# ADC_LCD_PROJECT.net
KiCad netlist of a schematic drawn in Altium Designer
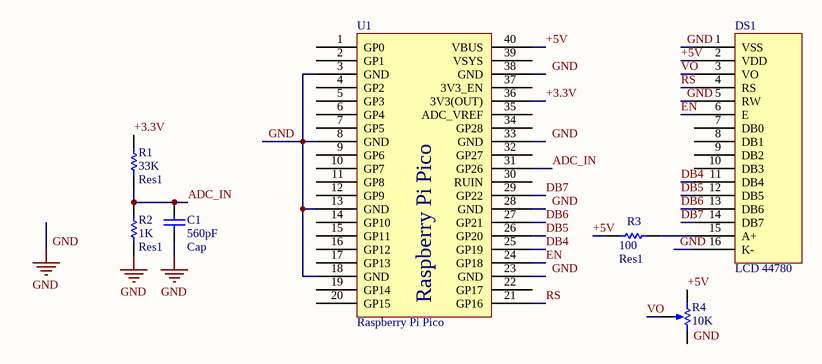
[diagram p0: ADC_LCD_PROJECT.SchDoc]

(export (version "E")
  (design (tool "Eeschema 10.0.6"))
  (components
    (comp (ref "C1")
      (value "Cap")
      (footprint "RAD-0.3")
      (description "Capacitor")
      (fields (field (name "ALTIUM_VALUE") "560pF") (field (name "PUBLISHER") "Altium Limited"))
      (libsource (lib "Miscellaneous Devices") (part "Cap"))
    )
    (comp (ref "DS1")
      (value "LCD 44780")
      (footprint "OLED 16x2")
      (libsource (lib "ECE Lib 22") (part "LCD 44780"))
    )
    (comp (ref "R1")
      (value "Res1")
      (footprint "AXIAL-0.3")
      (description "Resistor")
      (fields (field (name "ALTIUM_VALUE") "33K") (field (name "PUBLISHER") "Altium Limited"))
      (libsource (lib "Miscellaneous Devices") (part "Res1"))
    )
    (comp (ref "R2")
      (value "Res1")
      (footprint "AXIAL-0.3")
      (description "Resistor")
      (fields (field (name "ALTIUM_VALUE") "1K") (field (name "PUBLISHER") "Altium Limited"))
      (libsource (lib "Miscellaneous Devices") (part "Res1"))
    )
    (comp (ref "R3")
      (value "Res1")
      (footprint "AXIAL-0.3")
      (description "Resistor")
      (fields (field (name "ALTIUM_VALUE") "100") (field (name "PUBLISHER") "Altium Limited"))
      (libsource (lib "Miscellaneous Devices") (part "Res1"))
    )
    (comp (ref "R4")
      (value "10K")
      (footprint "POT inline wide")
      (description "Potentiometer")
      (fields (field (name "Comment") "RPot_1") (field (name "PUBLISHER") "Altium Limited"))
      (libsource (lib "ECE Lib 22") (part "RPot_3"))
    )
    (comp (ref "U1")
      (value "Raspberry Pi Pico")
      (footprint "Raspberry Pi Pico")
      (libsource (lib "ECE Lib 22") (part "Raspberry Pi Pico"))
    )
  )
  (nets
    (net (code "1") (name "/+3.3V") (class "Default")
      (node (ref "R1") (pin "2") (pinfunction "2_2") (pintype "passive"))
      (node (ref "U1") (pin "36") (pinfunction "3V3(OUT)_36") (pintype "passive"))
    )
    (net (code "2") (name "/+5V") (class "Default")
      (node (ref "DS1") (pin "2") (pinfunction "VDD_2") (pintype "passive"))
      (node (ref "R3") (pin "1") (pinfunction "1_1") (pintype "passive"))
      (node (ref "R4") (pin "1") (pinfunction "TOP_1") (pintype "passive"))
      (node (ref "U1") (pin "40") (pinfunction "VBUS_40") (pintype "passive"))
    )
    (net (code "3") (name "/ADC_IN") (class "Default")
      (node (ref "C1") (pin "2") (pinfunction "2_2") (pintype "passive"))
      (node (ref "R1") (pin "1") (pinfunction "1_1") (pintype "passive"))
      (node (ref "R2") (pin "2") (pinfunction "2_2") (pintype "passive"))
      (node (ref "U1") (pin "31") (pinfunction "GP26_31") (pintype "passive"))
    )
    (net (code "4") (name "/DB4") (class "Default")
      (node (ref "DS1") (pin "11") (pinfunction "DB4_11") (pintype "passive"))
      (node (ref "U1") (pin "25") (pinfunction "GP19_25") (pintype "passive"))
    )
    (net (code "5") (name "/DB5") (class "Default")
      (node (ref "DS1") (pin "12") (pinfunction "DB5_12") (pintype "passive"))
      (node (ref "U1") (pin "26") (pinfunction "GP20_26") (pintype "passive"))
    )
    (net (code "6") (name "/DB6") (class "Default")
      (node (ref "DS1") (pin "13") (pinfunction "DB6_13") (pintype "passive"))
      (node (ref "U1") (pin "27") (pinfunction "GP21_27") (pintype "passive"))
    )
    (net (code "7") (name "/DB7") (class "Default")
      (node (ref "DS1") (pin "14") (pinfunction "DB7_14") (pintype "passive"))
      (node (ref "U1") (pin "29") (pinfunction "GP22_29") (pintype "passive"))
    )
    (net (code "8") (name "/EN") (class "Default")
      (node (ref "DS1") (pin "6") (pinfunction "E_6") (pintype "passive"))
      (node (ref "U1") (pin "24") (pinfunction "GP18_24") (pintype "passive"))
    )
    (net (code "9") (name "/RS") (class "Default")
      (node (ref "DS1") (pin "4") (pinfunction "RS_4") (pintype "passive"))
      (node (ref "U1") (pin "21") (pinfunction "GP16_21") (pintype "passive"))
    )
    (net (code "10") (name "/VO") (class "Default")
      (node (ref "DS1") (pin "3") (pinfunction "VO_3") (pintype "passive"))
      (node (ref "R4") (pin "2") (pinfunction "TAP_2") (pintype "passive"))
    )
    (net (code "11") (name "GND") (class "Default")
      (node (ref "C1") (pin "1") (pinfunction "1_1") (pintype "passive"))
      (node (ref "DS1") (pin "1") (pinfunction "VSS_1") (pintype "passive"))
      (node (ref "DS1") (pin "16") (pinfunction "K-_16") (pintype "passive"))
      (node (ref "DS1") (pin "5") (pinfunction "RW_5") (pintype "passive"))
      (node (ref "R2") (pin "1") (pinfunction "1_1") (pintype "passive"))
      (node (ref "R4") (pin "3") (pinfunction "BOT_3") (pintype "passive"))
      (node (ref "U1") (pin "13") (pinfunction "GND_13") (pintype "passive"))
      (node (ref "U1") (pin "18") (pinfunction "GND_18") (pintype "passive"))
      (node (ref "U1") (pin "23") (pinfunction "GND_23") (pintype "passive"))
      (node (ref "U1") (pin "28") (pinfunction "GND_28") (pintype "passive"))
      (node (ref "U1") (pin "3") (pinfunction "GND_3") (pintype "passive"))
      (node (ref "U1") (pin "33") (pinfunction "GND_33") (pintype "passive"))
      (node (ref "U1") (pin "38") (pinfunction "GND_38") (pintype "passive"))
      (node (ref "U1") (pin "8") (pinfunction "GND_8") (pintype "passive"))
    )
    (net (code "12") (name "Net-(DS1-A+)") (class "Default")
      (node (ref "DS1") (pin "15") (pinfunction "A+_15") (pintype "passive"))
      (node (ref "R3") (pin "2") (pinfunction "2_2") (pintype "passive"))
    )
    (net (code "13") (name "unconnected-(DS1-DB0-Pad7)") (class "Default")
      (node (ref "DS1") (pin "7") (pinfunction "DB0_7") (pintype "passive"))
    )
    (net (code "14") (name "unconnected-(DS1-DB1-Pad8)") (class "Default")
      (node (ref "DS1") (pin "8") (pinfunction "DB1_8") (pintype "passive"))
    )
    (net (code "15") (name "unconnected-(DS1-DB2-Pad9)") (class "Default")
      (node (ref "DS1") (pin "9") (pinfunction "DB2_9") (pintype "passive"))
    )
    (net (code "16") (name "unconnected-(DS1-DB3-Pad10)") (class "Default")
      (node (ref "DS1") (pin "10") (pinfunction "DB3_10") (pintype "passive"))
    )
    (net (code "17") (name "unconnected-(U1-3V3_EN-Pad37)") (class "Default")
      (node (ref "U1") (pin "37") (pinfunction "3V3_EN_37") (pintype "passive"))
    )
    (net (code "18") (name "unconnected-(U1-ADC_VREF-Pad35)") (class "Default")
      (node (ref "U1") (pin "35") (pinfunction "ADC_VREF_35") (pintype "passive"))
    )
    (net (code "19") (name "unconnected-(U1-GP0-Pad1)") (class "Default")
      (node (ref "U1") (pin "1") (pinfunction "GP0_1") (pintype "passive"))
    )
    (net (code "20") (name "unconnected-(U1-GP1-Pad2)") (class "Default")
      (node (ref "U1") (pin "2") (pinfunction "GP1_2") (pintype "passive"))
    )
    (net (code "21") (name "unconnected-(U1-GP2-Pad4)") (class "Default")
      (node (ref "U1") (pin "4") (pinfunction "GP2_4") (pintype "passive"))
    )
    (net (code "22") (name "unconnected-(U1-GP3-Pad5)") (class "Default")
      (node (ref "U1") (pin "5") (pinfunction "GP3_5") (pintype "passive"))
    )
    (net (code "23") (name "unconnected-(U1-GP4-Pad6)") (class "Default")
      (node (ref "U1") (pin "6") (pinfunction "GP4_6") (pintype "passive"))
    )
    (net (code "24") (name "unconnected-(U1-GP5-Pad7)") (class "Default")
      (node (ref "U1") (pin "7") (pinfunction "GP5_7") (pintype "passive"))
    )
    (net (code "25") (name "unconnected-(U1-GP6-Pad9)") (class "Default")
      (node (ref "U1") (pin "9") (pinfunction "GP6_9") (pintype "passive"))
    )
    (net (code "26") (name "unconnected-(U1-GP7-Pad10)") (class "Default")
      (node (ref "U1") (pin "10") (pinfunction "GP7_10") (pintype "passive"))
    )
    (net (code "27") (name "unconnected-(U1-GP8-Pad11)") (class "Default")
      (node (ref "U1") (pin "11") (pinfunction "GP8_11") (pintype "passive"))
    )
    (net (code "28") (name "unconnected-(U1-GP9-Pad12)") (class "Default")
      (node (ref "U1") (pin "12") (pinfunction "GP9_12") (pintype "passive"))
    )
    (net (code "29") (name "unconnected-(U1-GP10-Pad14)") (class "Default")
      (node (ref "U1") (pin "14") (pinfunction "GP10_14") (pintype "passive"))
    )
    (net (code "30") (name "unconnected-(U1-GP11-Pad15)") (class "Default")
      (node (ref "U1") (pin "15") (pinfunction "GP11_15") (pintype "passive"))
    )
    (net (code "31") (name "unconnected-(U1-GP12-Pad16)") (class "Default")
      (node (ref "U1") (pin "16") (pinfunction "GP12_16") (pintype "passive"))
    )
    (net (code "32") (name "unconnected-(U1-GP13-Pad17)") (class "Default")
      (node (ref "U1") (pin "17") (pinfunction "GP13_17") (pintype "passive"))
    )
    (net (code "33") (name "unconnected-(U1-GP14-Pad19)") (class "Default")
      (node (ref "U1") (pin "19") (pinfunction "GP14_19") (pintype "passive"))
    )
    (net (code "34") (name "unconnected-(U1-GP15-Pad20)") (class "Default")
      (node (ref "U1") (pin "20") (pinfunction "GP15_20") (pintype "passive"))
    )
    (net (code "35") (name "unconnected-(U1-GP17-Pad22)") (class "Default")
      (node (ref "U1") (pin "22") (pinfunction "GP17_22") (pintype "passive"))
    )
    (net (code "36") (name "unconnected-(U1-GP27-Pad32)") (class "Default")
      (node (ref "U1") (pin "32") (pinfunction "GP27_32") (pintype "passive"))
    )
    (net (code "37") (name "unconnected-(U1-GP28-Pad34)") (class "Default")
      (node (ref "U1") (pin "34") (pinfunction "GP28_34") (pintype "passive"))
    )
    (net (code "38") (name "unconnected-(U1-RUIN-Pad30)") (class "Default")
      (node (ref "U1") (pin "30") (pinfunction "RUIN_30") (pintype "passive"))
    )
    (net (code "39") (name "unconnected-(U1-VSYS-Pad39)") (class "Default")
      (node (ref "U1") (pin "39") (pinfunction "VSYS_39") (pintype "passive"))
    )
  )
)
